# Main_Board.net
KiCad netlist of a schematic drawn in EAGLE
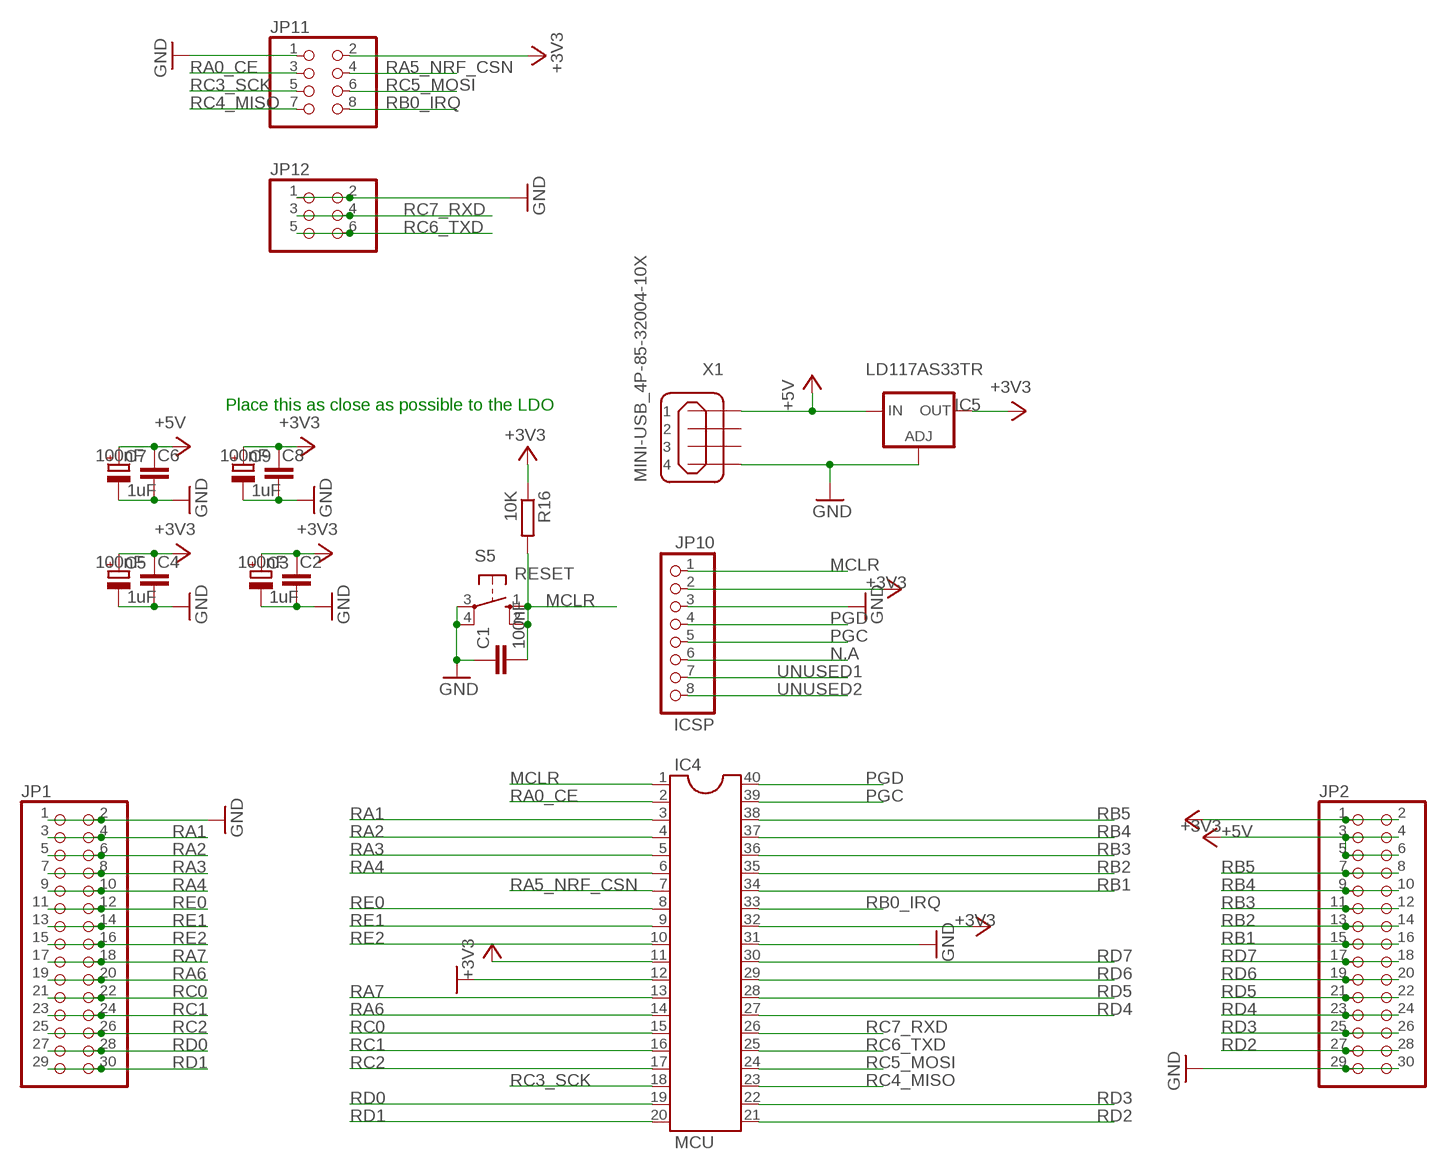
[diagram p0: schematic, sheet 1]
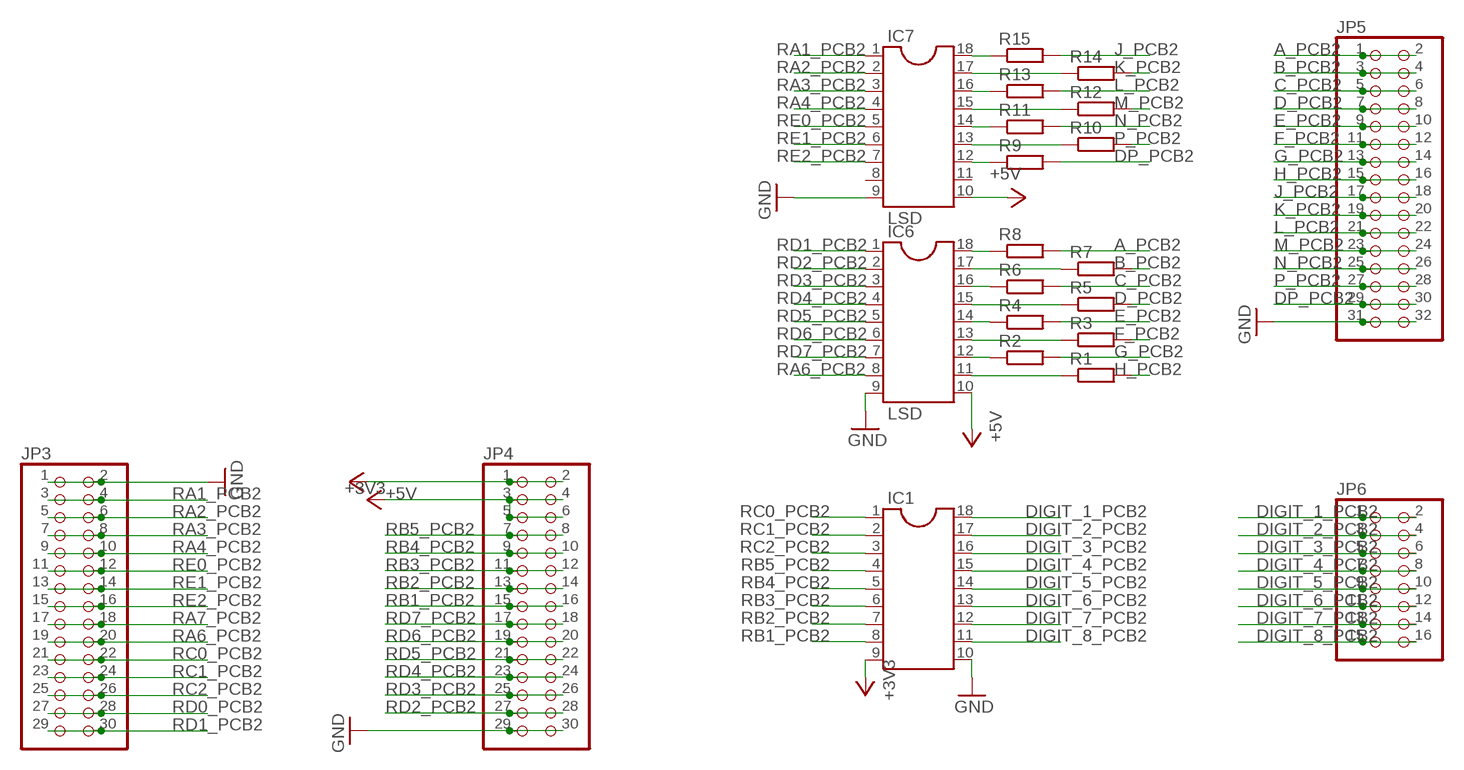
[diagram p1: schematic, sheet 2]
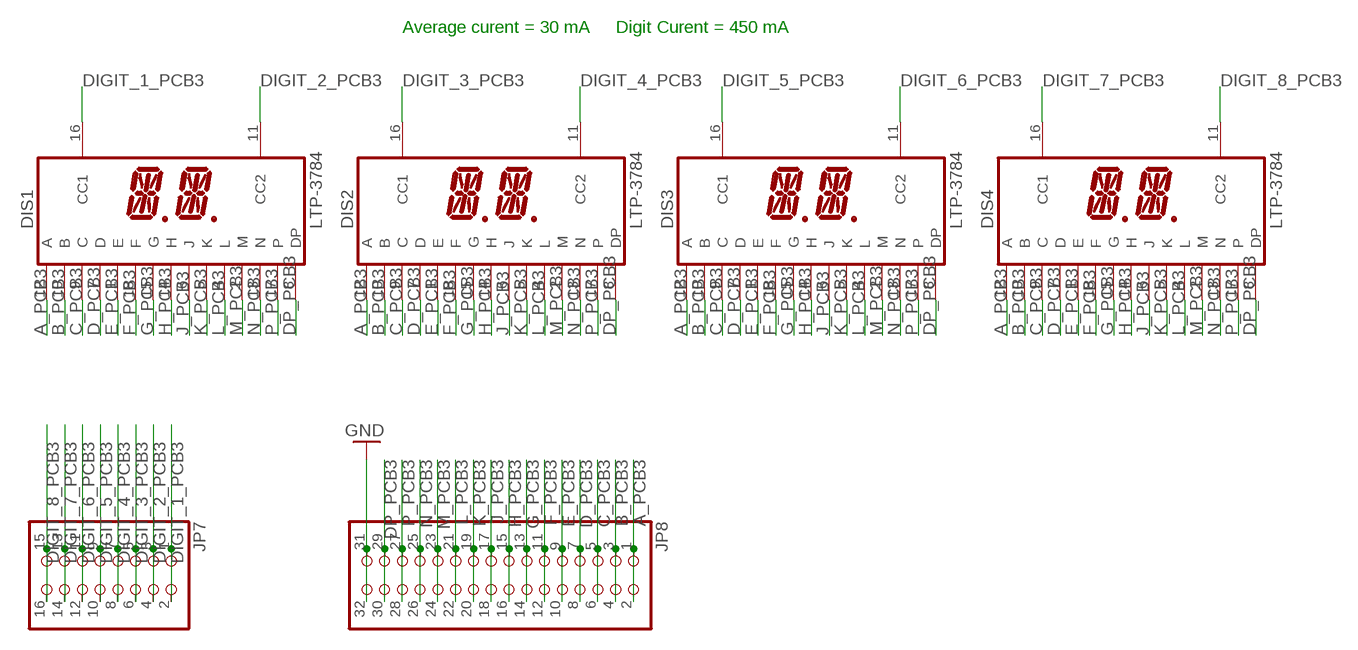
[diagram p2: schematic, sheet 3]

(export (version "E")
  (design (tool "Eeschema 10.0.6"))
  (components
    (comp (ref "IC1")
      (value "DIL18")
      (footprint "eagle-import:DIL18")
      (libsource (lib "eagle-import") (part "DIL18"))
    )
    (comp (ref "IC6")
      (value "LSD")
      (footprint "eagle-import:DIL18")
      (libsource (lib "eagle-import") (part "DIL18"))
    )
    (comp (ref "IC7")
      (value "LSD")
      (footprint "eagle-import:DIL18")
      (libsource (lib "eagle-import") (part "DIL18"))
    )
    (comp (ref "JP3")
      (value "PINHD-2X15")
      (footprint "eagle-import:2X15")
      (libsource (lib "eagle-import") (part "PINHD-2X15"))
    )
    (comp (ref "JP4")
      (value "PINHD-2X15")
      (footprint "eagle-import:2X15")
      (libsource (lib "eagle-import") (part "PINHD-2X15"))
    )
    (comp (ref "JP5")
      (value "PINHD-2X16")
      (footprint "eagle-import:2X16")
      (libsource (lib "eagle-import") (part "PINHD-2X16"))
    )
    (comp (ref "JP6")
      (value "PINHD-2X8")
      (footprint "eagle-import:2X08")
      (libsource (lib "eagle-import") (part "PINHD-2X8"))
    )
    (comp (ref "R1")
      (value "R-EU_R0805")
      (footprint "eagle-import:R0805")
      (libsource (lib "eagle-import") (part "R-EU_R0805"))
    )
    (comp (ref "R2")
      (value "R-EU_R0805")
      (footprint "eagle-import:R0805")
      (libsource (lib "eagle-import") (part "R-EU_R0805"))
    )
    (comp (ref "R3")
      (value "R-EU_R0805")
      (footprint "eagle-import:R0805")
      (libsource (lib "eagle-import") (part "R-EU_R0805"))
    )
    (comp (ref "R4")
      (value "R-EU_R0805")
      (footprint "eagle-import:R0805")
      (libsource (lib "eagle-import") (part "R-EU_R0805"))
    )
    (comp (ref "R5")
      (value "R-EU_R0805")
      (footprint "eagle-import:R0805")
      (libsource (lib "eagle-import") (part "R-EU_R0805"))
    )
    (comp (ref "R6")
      (value "R-EU_R0805")
      (footprint "eagle-import:R0805")
      (libsource (lib "eagle-import") (part "R-EU_R0805"))
    )
    (comp (ref "R7")
      (value "R-EU_R0805")
      (footprint "eagle-import:R0805")
      (libsource (lib "eagle-import") (part "R-EU_R0805"))
    )
    (comp (ref "R8")
      (value "R-EU_R0805")
      (footprint "eagle-import:R0805")
      (libsource (lib "eagle-import") (part "R-EU_R0805"))
    )
    (comp (ref "R9")
      (value "R-EU_R0805")
      (footprint "eagle-import:R0805")
      (libsource (lib "eagle-import") (part "R-EU_R0805"))
    )
    (comp (ref "R10")
      (value "R-EU_R0805")
      (footprint "eagle-import:R0805")
      (libsource (lib "eagle-import") (part "R-EU_R0805"))
    )
    (comp (ref "R11")
      (value "R-EU_R0805")
      (footprint "eagle-import:R0805")
      (libsource (lib "eagle-import") (part "R-EU_R0805"))
    )
    (comp (ref "R12")
      (value "R-EU_R0805")
      (footprint "eagle-import:R0805")
      (libsource (lib "eagle-import") (part "R-EU_R0805"))
    )
    (comp (ref "R13")
      (value "R-EU_R0805")
      (footprint "eagle-import:R0805")
      (libsource (lib "eagle-import") (part "R-EU_R0805"))
    )
    (comp (ref "R14")
      (value "R-EU_R0805")
      (footprint "eagle-import:R0805")
      (libsource (lib "eagle-import") (part "R-EU_R0805"))
    )
    (comp (ref "R15")
      (value "R-EU_R0805")
      (footprint "eagle-import:R0805")
      (libsource (lib "eagle-import") (part "R-EU_R0805"))
    )
    (comp (ref "DIS1")
      (value "LTP-3784")
      (footprint "eagle-import:LTP-3784")
      (libsource (lib "eagle-import") (part "LTP-3784"))
    )
    (comp (ref "DIS2")
      (value "LTP-3784")
      (footprint "eagle-import:LTP-3784")
      (libsource (lib "eagle-import") (part "LTP-3784"))
    )
    (comp (ref "DIS3")
      (value "LTP-3784")
      (footprint "eagle-import:LTP-3784")
      (libsource (lib "eagle-import") (part "LTP-3784"))
    )
    (comp (ref "DIS4")
      (value "LTP-3784")
      (footprint "eagle-import:LTP-3784")
      (libsource (lib "eagle-import") (part "LTP-3784"))
    )
    (comp (ref "JP7")
      (value "PINHD-2X8")
      (footprint "eagle-import:2X08")
      (libsource (lib "eagle-import") (part "PINHD-2X8"))
    )
    (comp (ref "JP8")
      (value "PINHD-2X16")
      (footprint "eagle-import:2X16")
      (libsource (lib "eagle-import") (part "PINHD-2X16"))
    )
    (comp (ref "C1")
      (value "100nF")
      (footprint "eagle-import:C025-025X050")
      (libsource (lib "eagle-import") (part "C-EU025-025X050"))
    )
    (comp (ref "C2")
      (value "100nF")
      (footprint "eagle-import:C025-025X050")
      (libsource (lib "eagle-import") (part "C-EU025-025X050"))
    )
    (comp (ref "C3")
      (value "1uF")
      (footprint "eagle-import:E1,8-4")
      (libsource (lib "eagle-import") (part "CPOL-EUE1.8-4"))
    )
    (comp (ref "C4")
      (value "100nF")
      (footprint "eagle-import:C025-025X050")
      (libsource (lib "eagle-import") (part "C-EU025-025X050"))
    )
    (comp (ref "C5")
      (value "1uF")
      (footprint "eagle-import:E1,8-4")
      (libsource (lib "eagle-import") (part "CPOL-EUE1.8-4"))
    )
    (comp (ref "C6")
      (value "100nF")
      (footprint "eagle-import:C025-025X050")
      (libsource (lib "eagle-import") (part "C-EU025-025X050"))
    )
    (comp (ref "C7")
      (value "1uF")
      (footprint "eagle-import:E1,8-4")
      (libsource (lib "eagle-import") (part "CPOL-EUE1.8-4"))
    )
    (comp (ref "C8")
      (value "100nF")
      (footprint "eagle-import:C025-025X050")
      (libsource (lib "eagle-import") (part "C-EU025-025X050"))
    )
    (comp (ref "C9")
      (value "1uF")
      (footprint "eagle-import:E1,8-4")
      (libsource (lib "eagle-import") (part "CPOL-EUE1.8-4"))
    )
    (comp (ref "IC4")
      (value "MCU")
      (footprint "eagle-import:DIL40")
      (libsource (lib "eagle-import") (part "DIL40"))
    )
    (comp (ref "IC5")
      (value "LD117AS33TR")
      (footprint "eagle-import:SOT223")
      (libsource (lib "eagle-import") (part "LD117A?S33TR"))
    )
    (comp (ref "JP1")
      (value "PINHD-2X15")
      (footprint "eagle-import:2X15")
      (libsource (lib "eagle-import") (part "PINHD-2X15"))
    )
    (comp (ref "JP2")
      (value "PINHD-2X15")
      (footprint "eagle-import:2X15")
      (libsource (lib "eagle-import") (part "PINHD-2X15"))
    )
    (comp (ref "JP10")
      (value "ICSP")
      (footprint "eagle-import:1X08")
      (libsource (lib "eagle-import") (part "PINHD-1X8"))
    )
    (comp (ref "JP11")
      (value "PINHD-2X4")
      (footprint "eagle-import:2X04")
      (libsource (lib "eagle-import") (part "PINHD-2X4"))
    )
    (comp (ref "JP12")
      (value "PINHD-2X3")
      (footprint "eagle-import:2X03")
      (libsource (lib "eagle-import") (part "PINHD-2X3"))
    )
    (comp (ref "R16")
      (value "10K")
      (footprint "eagle-import:0207_10")
      (libsource (lib "eagle-import") (part "R-EU_0207/10"))
    )
    (comp (ref "S5")
      (value "RESET")
      (footprint "eagle-import:B3F-10XX")
      (fields (field (name "MPN") "B3F-1000"))
      (libsource (lib "eagle-import") (part "10-XX"))
    )
    (comp (ref "X1")
      (value "MINI-USB_4P-85-32004-10X")
      (footprint "eagle-import:85-32004-10X")
      (libsource (lib "eagle-import") (part "MINI-USB_4P-85-32004-10X"))
    )
  )
  (nets
    (net (code "1") (name "+3V3") (class "Default")
      (node (ref "C2") (pin "2") (pinfunction "2_2") (pintype "passive"))
      (node (ref "C3") (pin "+") (pinfunction "+_+") (pintype "passive"))
      (node (ref "C4") (pin "2") (pinfunction "2_2") (pintype "passive"))
      (node (ref "C5") (pin "+") (pinfunction "+_+") (pintype "passive"))
      (node (ref "C8") (pin "2") (pinfunction "2_2") (pintype "passive"))
      (node (ref "C9") (pin "+") (pinfunction "+_+") (pintype "passive"))
      (node (ref "IC1") (pin "9") (pinfunction "9_9") (pintype "passive"))
      (node (ref "IC4") (pin "11") (pinfunction "11_11") (pintype "passive"))
      (node (ref "IC4") (pin "32") (pinfunction "32_32") (pintype "passive"))
      (node (ref "IC5") (pin "4") (pinfunction "OUT_4") (pintype "passive"))
      (node (ref "JP10") (pin "2") (pinfunction "2_2") (pintype "passive"))
      (node (ref "JP11") (pin "2") (pinfunction "2_2") (pintype "passive"))
      (node (ref "JP2") (pin "1") (pinfunction "1_1") (pintype "passive"))
      (node (ref "JP2") (pin "2") (pinfunction "2_2") (pintype "passive"))
      (node (ref "JP4") (pin "1") (pinfunction "1_1") (pintype "passive"))
      (node (ref "JP4") (pin "2") (pinfunction "2_2") (pintype "passive"))
      (node (ref "R16") (pin "1") (pinfunction "1_1") (pintype "passive"))
    )
    (net (code "2") (name "+5V") (class "Default")
      (node (ref "C6") (pin "2") (pinfunction "2_2") (pintype "passive"))
      (node (ref "C7") (pin "+") (pinfunction "+_+") (pintype "passive"))
      (node (ref "IC5") (pin "3") (pinfunction "IN_3") (pintype "input"))
      (node (ref "IC6") (pin "10") (pinfunction "10_10") (pintype "passive"))
      (node (ref "IC7") (pin "10") (pinfunction "10_10") (pintype "passive"))
      (node (ref "JP2") (pin "3") (pinfunction "3_3") (pintype "passive"))
      (node (ref "JP2") (pin "4") (pinfunction "4_4") (pintype "passive"))
      (node (ref "JP2") (pin "5") (pinfunction "5_5") (pintype "passive"))
      (node (ref "JP2") (pin "6") (pinfunction "6_6") (pintype "passive"))
      (node (ref "JP4") (pin "3") (pinfunction "3_3") (pintype "passive"))
      (node (ref "JP4") (pin "4") (pinfunction "4_4") (pintype "passive"))
      (node (ref "JP4") (pin "5") (pinfunction "5_5") (pintype "passive"))
      (node (ref "JP4") (pin "6") (pinfunction "6_6") (pintype "passive"))
      (node (ref "X1") (pin "1") (pinfunction "1_1") (pintype "passive"))
    )
    (net (code "3") (name "A_PCB2") (class "Default")
      (node (ref "JP5") (pin "1") (pinfunction "1_1") (pintype "passive"))
      (node (ref "JP5") (pin "2") (pinfunction "2_2") (pintype "passive"))
      (node (ref "R8") (pin "2") (pinfunction "2_2") (pintype "passive"))
    )
    (net (code "4") (name "A_PCB3") (class "Default")
      (node (ref "DIS1") (pin "12") (pinfunction "A_12") (pintype "passive"))
      (node (ref "DIS2") (pin "12") (pinfunction "A_12") (pintype "passive"))
      (node (ref "DIS3") (pin "12") (pinfunction "A_12") (pintype "passive"))
      (node (ref "DIS4") (pin "12") (pinfunction "A_12") (pintype "passive"))
      (node (ref "JP8") (pin "1") (pinfunction "1_1") (pintype "passive"))
      (node (ref "JP8") (pin "2") (pinfunction "2_2") (pintype "passive"))
    )
    (net (code "5") (name "B_PCB2") (class "Default")
      (node (ref "JP5") (pin "3") (pinfunction "3_3") (pintype "passive"))
      (node (ref "JP5") (pin "4") (pinfunction "4_4") (pintype "passive"))
      (node (ref "R7") (pin "2") (pinfunction "2_2") (pintype "passive"))
    )
    (net (code "6") (name "B_PCB3") (class "Default")
      (node (ref "DIS1") (pin "10") (pinfunction "B_10") (pintype "passive"))
      (node (ref "DIS2") (pin "10") (pinfunction "B_10") (pintype "passive"))
      (node (ref "DIS3") (pin "10") (pinfunction "B_10") (pintype "passive"))
      (node (ref "DIS4") (pin "10") (pinfunction "B_10") (pintype "passive"))
      (node (ref "JP8") (pin "3") (pinfunction "3_3") (pintype "passive"))
      (node (ref "JP8") (pin "4") (pinfunction "4_4") (pintype "passive"))
    )
    (net (code "7") (name "C_PCB2") (class "Default")
      (node (ref "JP5") (pin "5") (pinfunction "5_5") (pintype "passive"))
      (node (ref "JP5") (pin "6") (pinfunction "6_6") (pintype "passive"))
      (node (ref "R6") (pin "2") (pinfunction "2_2") (pintype "passive"))
    )
    (net (code "8") (name "C_PCB3") (class "Default")
      (node (ref "DIS1") (pin "9") (pinfunction "C_9") (pintype "passive"))
      (node (ref "DIS2") (pin "9") (pinfunction "C_9") (pintype "passive"))
      (node (ref "DIS3") (pin "9") (pinfunction "C_9") (pintype "passive"))
      (node (ref "DIS4") (pin "9") (pinfunction "C_9") (pintype "passive"))
      (node (ref "JP8") (pin "5") (pinfunction "5_5") (pintype "passive"))
      (node (ref "JP8") (pin "6") (pinfunction "6_6") (pintype "passive"))
    )
    (net (code "9") (name "DIGIT_1_PCB2") (class "Default")
      (node (ref "IC1") (pin "18") (pinfunction "18_18") (pintype "passive"))
      (node (ref "JP6") (pin "1") (pinfunction "1_1") (pintype "passive"))
      (node (ref "JP6") (pin "2") (pinfunction "2_2") (pintype "passive"))
    )
    (net (code "10") (name "DIGIT_1_PCB3") (class "Default")
      (node (ref "DIS1") (pin "16") (pinfunction "CC1_16") (pintype "passive"))
      (node (ref "JP7") (pin "1") (pinfunction "1_1") (pintype "passive"))
      (node (ref "JP7") (pin "2") (pinfunction "2_2") (pintype "passive"))
    )
    (net (code "11") (name "DIGIT_2_PCB2") (class "Default")
      (node (ref "IC1") (pin "17") (pinfunction "17_17") (pintype "passive"))
      (node (ref "JP6") (pin "3") (pinfunction "3_3") (pintype "passive"))
      (node (ref "JP6") (pin "4") (pinfunction "4_4") (pintype "passive"))
    )
    (net (code "12") (name "DIGIT_2_PCB3") (class "Default")
      (node (ref "DIS1") (pin "11") (pinfunction "CC2_11") (pintype "passive"))
      (node (ref "JP7") (pin "3") (pinfunction "3_3") (pintype "passive"))
      (node (ref "JP7") (pin "4") (pinfunction "4_4") (pintype "passive"))
    )
    (net (code "13") (name "DIGIT_3_PCB2") (class "Default")
      (node (ref "IC1") (pin "16") (pinfunction "16_16") (pintype "passive"))
      (node (ref "JP6") (pin "5") (pinfunction "5_5") (pintype "passive"))
      (node (ref "JP6") (pin "6") (pinfunction "6_6") (pintype "passive"))
    )
    (net (code "14") (name "DIGIT_3_PCB3") (class "Default")
      (node (ref "DIS2") (pin "16") (pinfunction "CC1_16") (pintype "passive"))
      (node (ref "JP7") (pin "5") (pinfunction "5_5") (pintype "passive"))
      (node (ref "JP7") (pin "6") (pinfunction "6_6") (pintype "passive"))
    )
    (net (code "15") (name "DIGIT_4_PCB2") (class "Default")
      (node (ref "IC1") (pin "15") (pinfunction "15_15") (pintype "passive"))
      (node (ref "JP6") (pin "7") (pinfunction "7_7") (pintype "passive"))
      (node (ref "JP6") (pin "8") (pinfunction "8_8") (pintype "passive"))
    )
    (net (code "16") (name "DIGIT_4_PCB3") (class "Default")
      (node (ref "DIS2") (pin "11") (pinfunction "CC2_11") (pintype "passive"))
      (node (ref "JP7") (pin "7") (pinfunction "7_7") (pintype "passive"))
      (node (ref "JP7") (pin "8") (pinfunction "8_8") (pintype "passive"))
    )
    (net (code "17") (name "DIGIT_5_PCB2") (class "Default")
      (node (ref "IC1") (pin "14") (pinfunction "14_14") (pintype "passive"))
      (node (ref "JP6") (pin "10") (pinfunction "10_10") (pintype "passive"))
      (node (ref "JP6") (pin "9") (pinfunction "9_9") (pintype "passive"))
    )
    (net (code "18") (name "DIGIT_5_PCB3") (class "Default")
      (node (ref "DIS3") (pin "16") (pinfunction "CC1_16") (pintype "passive"))
      (node (ref "JP7") (pin "10") (pinfunction "10_10") (pintype "passive"))
      (node (ref "JP7") (pin "9") (pinfunction "9_9") (pintype "passive"))
    )
    (net (code "19") (name "DIGIT_6_PCB2") (class "Default")
      (node (ref "IC1") (pin "13") (pinfunction "13_13") (pintype "passive"))
      (node (ref "JP6") (pin "11") (pinfunction "11_11") (pintype "passive"))
      (node (ref "JP6") (pin "12") (pinfunction "12_12") (pintype "passive"))
    )
    (net (code "20") (name "DIGIT_6_PCB3") (class "Default")
      (node (ref "DIS3") (pin "11") (pinfunction "CC2_11") (pintype "passive"))
      (node (ref "JP7") (pin "11") (pinfunction "11_11") (pintype "passive"))
      (node (ref "JP7") (pin "12") (pinfunction "12_12") (pintype "passive"))
    )
    (net (code "21") (name "DIGIT_7_PCB2") (class "Default")
      (node (ref "IC1") (pin "12") (pinfunction "12_12") (pintype "passive"))
      (node (ref "JP6") (pin "13") (pinfunction "13_13") (pintype "passive"))
      (node (ref "JP6") (pin "14") (pinfunction "14_14") (pintype "passive"))
    )
    (net (code "22") (name "DIGIT_7_PCB3") (class "Default")
      (node (ref "DIS4") (pin "16") (pinfunction "CC1_16") (pintype "passive"))
      (node (ref "JP7") (pin "13") (pinfunction "13_13") (pintype "passive"))
      (node (ref "JP7") (pin "14") (pinfunction "14_14") (pintype "passive"))
    )
    (net (code "23") (name "DIGIT_8_PCB2") (class "Default")
      (node (ref "IC1") (pin "11") (pinfunction "11_11") (pintype "passive"))
      (node (ref "JP6") (pin "15") (pinfunction "15_15") (pintype "passive"))
      (node (ref "JP6") (pin "16") (pinfunction "16_16") (pintype "passive"))
    )
    (net (code "24") (name "DIGIT_8_PCB3") (class "Default")
      (node (ref "DIS4") (pin "11") (pinfunction "CC2_11") (pintype "passive"))
      (node (ref "JP7") (pin "15") (pinfunction "15_15") (pintype "passive"))
      (node (ref "JP7") (pin "16") (pinfunction "16_16") (pintype "passive"))
    )
    (net (code "25") (name "DP_PCB2") (class "Default")
      (node (ref "JP5") (pin "29") (pinfunction "29_29") (pintype "passive"))
      (node (ref "JP5") (pin "30") (pinfunction "30_30") (pintype "passive"))
      (node (ref "R9") (pin "2") (pinfunction "2_2") (pintype "passive"))
    )
    (net (code "26") (name "DP_PCB3") (class "Default")
      (node (ref "DIS1") (pin "8") (pinfunction "DP_8") (pintype "passive"))
      (node (ref "DIS2") (pin "8") (pinfunction "DP_8") (pintype "passive"))
      (node (ref "DIS3") (pin "8") (pinfunction "DP_8") (pintype "passive"))
      (node (ref "DIS4") (pin "8") (pinfunction "DP_8") (pintype "passive"))
      (node (ref "JP8") (pin "29") (pinfunction "29_29") (pintype "passive"))
      (node (ref "JP8") (pin "30") (pinfunction "30_30") (pintype "passive"))
    )
    (net (code "27") (name "D_PCB2") (class "Default")
      (node (ref "JP5") (pin "7") (pinfunction "7_7") (pintype "passive"))
      (node (ref "JP5") (pin "8") (pinfunction "8_8") (pintype "passive"))
      (node (ref "R5") (pin "2") (pinfunction "2_2") (pintype "passive"))
    )
    (net (code "28") (name "D_PCB3") (class "Default")
      (node (ref "DIS1") (pin "7") (pinfunction "D_7") (pintype "passive"))
      (node (ref "DIS2") (pin "7") (pinfunction "D_7") (pintype "passive"))
      (node (ref "DIS3") (pin "7") (pinfunction "D_7") (pintype "passive"))
      (node (ref "DIS4") (pin "7") (pinfunction "D_7") (pintype "passive"))
      (node (ref "JP8") (pin "7") (pinfunction "7_7") (pintype "passive"))
      (node (ref "JP8") (pin "8") (pinfunction "8_8") (pintype "passive"))
    )
    (net (code "29") (name "E_PCB2") (class "Default")
      (node (ref "JP5") (pin "10") (pinfunction "10_10") (pintype "passive"))
      (node (ref "JP5") (pin "9") (pinfunction "9_9") (pintype "passive"))
      (node (ref "R4") (pin "2") (pinfunction "2_2") (pintype "passive"))
    )
    (net (code "30") (name "E_PCB3") (class "Default")
      (node (ref "DIS1") (pin "1") (pinfunction "E_1") (pintype "passive"))
      (node (ref "DIS2") (pin "1") (pinfunction "E_1") (pintype "passive"))
      (node (ref "DIS3") (pin "1") (pinfunction "E_1") (pintype "passive"))
      (node (ref "DIS4") (pin "1") (pinfunction "E_1") (pintype "passive"))
      (node (ref "JP8") (pin "10") (pinfunction "10_10") (pintype "passive"))
      (node (ref "JP8") (pin "9") (pinfunction "9_9") (pintype "passive"))
    )
    (net (code "31") (name "F_PCB2") (class "Default")
      (node (ref "JP5") (pin "11") (pinfunction "11_11") (pintype "passive"))
      (node (ref "JP5") (pin "12") (pinfunction "12_12") (pintype "passive"))
      (node (ref "R3") (pin "2") (pinfunction "2_2") (pintype "passive"))
    )
    (net (code "32") (name "F_PCB3") (class "Default")
      (node (ref "DIS1") (pin "18") (pinfunction "F_18") (pintype "passive"))
      (node (ref "DIS2") (pin "18") (pinfunction "F_18") (pintype "passive"))
      (node (ref "DIS3") (pin "18") (pinfunction "F_18") (pintype "passive"))
      (node (ref "DIS4") (pin "18") (pinfunction "F_18") (pintype "passive"))
      (node (ref "JP8") (pin "11") (pinfunction "11_11") (pintype "passive"))
      (node (ref "JP8") (pin "12") (pinfunction "12_12") (pintype "passive"))
    )
    (net (code "33") (name "GND") (class "Default")
      (node (ref "C1") (pin "1") (pinfunction "1_1") (pintype "passive"))
      (node (ref "C2") (pin "1") (pinfunction "1_1") (pintype "passive"))
      (node (ref "C3") (pin "-") (pinfunction "-_-") (pintype "passive"))
      (node (ref "C4") (pin "1") (pinfunction "1_1") (pintype "passive"))
      (node (ref "C5") (pin "-") (pinfunction "-_-") (pintype "passive"))
      (node (ref "C6") (pin "1") (pinfunction "1_1") (pintype "passive"))
      (node (ref "C7") (pin "-") (pinfunction "-_-") (pintype "passive"))
      (node (ref "C8") (pin "1") (pinfunction "1_1") (pintype "passive"))
      (node (ref "C9") (pin "-") (pinfunction "-_-") (pintype "passive"))
      (node (ref "IC1") (pin "10") (pinfunction "10_10") (pintype "passive"))
      (node (ref "IC4") (pin "12") (pinfunction "12_12") (pintype "passive"))
      (node (ref "IC4") (pin "31") (pinfunction "31_31") (pintype "passive"))
      (node (ref "IC5") (pin "1") (pinfunction "ADJ_1") (pintype "input"))
      (node (ref "IC6") (pin "9") (pinfunction "9_9") (pintype "passive"))
      (node (ref "IC7") (pin "9") (pinfunction "9_9") (pintype "passive"))
      (node (ref "JP1") (pin "1") (pinfunction "1_1") (pintype "passive"))
      (node (ref "JP1") (pin "2") (pinfunction "2_2") (pintype "passive"))
      (node (ref "JP10") (pin "3") (pinfunction "3_3") (pintype "passive"))
      (node (ref "JP11") (pin "1") (pinfunction "1_1") (pintype "passive"))
      (node (ref "JP12") (pin "1") (pinfunction "1_1") (pintype "passive"))
      (node (ref "JP12") (pin "2") (pinfunction "2_2") (pintype "passive"))
      (node (ref "JP2") (pin "29") (pinfunction "29_29") (pintype "passive"))
      (node (ref "JP2") (pin "30") (pinfunction "30_30") (pintype "passive"))
      (node (ref "JP3") (pin "1") (pinfunction "1_1") (pintype "passive"))
      (node (ref "JP3") (pin "2") (pinfunction "2_2") (pintype "passive"))
      (node (ref "JP4") (pin "29") (pinfunction "29_29") (pintype "passive"))
      (node (ref "JP4") (pin "30") (pinfunction "30_30") (pintype "passive"))
      (node (ref "JP5") (pin "31") (pinfunction "31_31") (pintype "passive"))
      (node (ref "JP5") (pin "32") (pinfunction "32_32") (pintype "passive"))
      (node (ref "JP8") (pin "31") (pinfunction "31_31") (pintype "passive"))
      (node (ref "JP8") (pin "32") (pinfunction "32_32") (pintype "passive"))
      (node (ref "S5") (pin "3") (pinfunction "P_3") (pintype "passive"))
      (node (ref "S5") (pin "4") (pinfunction "P1_4") (pintype "passive"))
      (node (ref "X1") (pin "4") (pinfunction "4_4") (pintype "passive"))
    )
    (net (code "34") (name "G_PCB2") (class "Default")
      (node (ref "JP5") (pin "13") (pinfunction "13_13") (pintype "passive"))
      (node (ref "JP5") (pin "14") (pinfunction "14_14") (pintype "passive"))
      (node (ref "R2") (pin "2") (pinfunction "2_2") (pintype "passive"))
    )
    (net (code "35") (name "G_PCB3") (class "Default")
      (node (ref "DIS1") (pin "15") (pinfunction "G_15") (pintype "passive"))
      (node (ref "DIS2") (pin "15") (pinfunction "G_15") (pintype "passive"))
      (node (ref "DIS3") (pin "15") (pinfunction "G_15") (pintype "passive"))
      (node (ref "DIS4") (pin "15") (pinfunction "G_15") (pintype "passive"))
      (node (ref "JP8") (pin "13") (pinfunction "13_13") (pintype "passive"))
      (node (ref "JP8") (pin "14") (pinfunction "14_14") (pintype "passive"))
    )
    (net (code "36") (name "H_PCB2") (class "Default")
      (node (ref "JP5") (pin "15") (pinfunction "15_15") (pintype "passive"))
      (node (ref "JP5") (pin "16") (pinfunction "16_16") (pintype "passive"))
      (node (ref "R1") (pin "2") (pinfunction "2_2") (pintype "passive"))
    )
    (net (code "37") (name "H_PCB3") (class "Default")
      (node (ref "DIS1") (pin "14") (pinfunction "H_14") (pintype "passive"))
      (node (ref "DIS2") (pin "14") (pinfunction "H_14") (pintype "passive"))
      (node (ref "DIS3") (pin "14") (pinfunction "H_14") (pintype "passive"))
      (node (ref "DIS4") (pin "14") (pinfunction "H_14") (pintype "passive"))
      (node (ref "JP8") (pin "15") (pinfunction "15_15") (pintype "passive"))
      (node (ref "JP8") (pin "16") (pinfunction "16_16") (pintype "passive"))
    )
    (net (code "38") (name "J_PCB2") (class "Default")
      (node (ref "JP5") (pin "17") (pinfunction "17_17") (pintype "passive"))
      (node (ref "JP5") (pin "18") (pinfunction "18_18") (pintype "passive"))
      (node (ref "R15") (pin "2") (pinfunction "2_2") (pintype "passive"))
    )
    (net (code "39") (name "J_PCB3") (class "Default")
      (node (ref "DIS1") (pin "6") (pinfunction "J_6") (pintype "passive"))
      (node (ref "DIS2") (pin "6") (pinfunction "J_6") (pintype "passive"))
      (node (ref "DIS3") (pin "6") (pinfunction "J_6") (pintype "passive"))
      (node (ref "DIS4") (pin "6") (pinfunction "J_6") (pintype "passive"))
      (node (ref "JP8") (pin "17") (pinfunction "17_17") (pintype "passive"))
      (node (ref "JP8") (pin "18") (pinfunction "18_18") (pintype "passive"))
    )
    (net (code "40") (name "K_PCB2") (class "Default")
      (node (ref "JP5") (pin "19") (pinfunction "19_19") (pintype "passive"))
      (node (ref "JP5") (pin "20") (pinfunction "20_20") (pintype "passive"))
      (node (ref "R14") (pin "2") (pinfunction "2_2") (pintype "passive"))
    )
    (net (code "41") (name "K_PCB3") (class "Default")
      (node (ref "DIS1") (pin "5") (pinfunction "K_5") (pintype "passive"))
      (node (ref "DIS2") (pin "5") (pinfunction "K_5") (pintype "passive"))
      (node (ref "DIS3") (pin "5") (pinfunction "K_5") (pintype "passive"))
      (node (ref "DIS4") (pin "5") (pinfunction "K_5") (pintype "passive"))
      (node (ref "JP8") (pin "19") (pinfunction "19_19") (pintype "passive"))
      (node (ref "JP8") (pin "20") (pinfunction "20_20") (pintype "passive"))
    )
    (net (code "42") (name "L_PCB2") (class "Default")
      (node (ref "JP5") (pin "21") (pinfunction "21_21") (pintype "passive"))
      (node (ref "JP5") (pin "22") (pinfunction "22_22") (pintype "passive"))
      (node (ref "R13") (pin "2") (pinfunction "2_2") (pintype "passive"))
    )
    (net (code "43") (name "L_PCB3") (class "Default")
      (node (ref "DIS1") (pin "4") (pinfunction "L_4") (pintype "passive"))
      (node (ref "DIS2") (pin "4") (pinfunction "L_4") (pintype "passive"))
      (node (ref "DIS3") (pin "4") (pinfunction "L_4") (pintype "passive"))
      (node (ref "DIS4") (pin "4") (pinfunction "L_4") (pintype "passive"))
      (node (ref "JP8") (pin "21") (pinfunction "21_21") (pintype "passive"))
      (node (ref "JP8") (pin "22") (pinfunction "22_22") (pintype "passive"))
    )
    (net (code "44") (name "MCLR") (class "Default")
      (node (ref "C1") (pin "2") (pinfunction "2_2") (pintype "passive"))
      (node (ref "IC4") (pin "1") (pinfunction "1_1") (pintype "passive"))
      (node (ref "JP10") (pin "1") (pinfunction "1_1") (pintype "passive"))
      (node (ref "R16") (pin "2") (pinfunction "2_2") (pintype "passive"))
      (node (ref "S5") (pin "1") (pinfunction "S_1") (pintype "passive"))
      (node (ref "S5") (pin "2") (pinfunction "S1_2") (pintype "passive"))
    )
    (net (code "45") (name "M_PCB2") (class "Default")
      (node (ref "JP5") (pin "23") (pinfunction "23_23") (pintype "passive"))
      (node (ref "JP5") (pin "24") (pinfunction "24_24") (pintype "passive"))
      (node (ref "R12") (pin "2") (pinfunction "2_2") (pintype "passive"))
    )
    (net (code "46") (name "M_PCB3") (class "Default")
      (node (ref "DIS1") (pin "2") (pinfunction "M_2") (pintype "passive"))
      (node (ref "DIS2") (pin "2") (pinfunction "M_2") (pintype "passive"))
      (node (ref "DIS3") (pin "2") (pinfunction "M_2") (pintype "passive"))
      (node (ref "DIS4") (pin "2") (pinfunction "M_2") (pintype "passive"))
      (node (ref "JP8") (pin "23") (pinfunction "23_23") (pintype "passive"))
      (node (ref "JP8") (pin "24") (pinfunction "24_24") (pintype "passive"))
    )
    (net (code "47") (name "N.A") (class "Default")
      (node (ref "JP10") (pin "6") (pinfunction "6_6") (pintype "passive"))
    )
    (net (code "48") (name "N_PCB2") (class "Default")
      (node (ref "JP5") (pin "25") (pinfunction "25_25") (pintype "passive"))
      (node (ref "JP5") (pin "26") (pinfunction "26_26") (pintype "passive"))
      (node (ref "R11") (pin "2") (pinfunction "2_2") (pintype "passive"))
    )
    (net (code "49") (name "N_PCB3") (class "Default")
      (node (ref "DIS1") (pin "13") (pinfunction "N_13") (pintype "passive"))
      (node (ref "DIS2") (pin "13") (pinfunction "N_13") (pintype "passive"))
      (node (ref "DIS3") (pin "13") (pinfunction "N_13") (pintype "passive"))
      (node (ref "DIS4") (pin "13") (pinfunction "N_13") (pintype "passive"))
      (node (ref "JP8") (pin "25") (pinfunction "25_25") (pintype "passive"))
      (node (ref "JP8") (pin "26") (pinfunction "26_26") (pintype "passive"))
    )
    (net (code "50") (name "Net-(IC6-Pad11)") (class "Default")
      (node (ref "IC6") (pin "11") (pinfunction "11_11") (pintype "passive"))
      (node (ref "R1") (pin "1") (pinfunction "1_1") (pintype "passive"))
    )
    (net (code "51") (name "Net-(IC6-Pad12)") (class "Default")
      (node (ref "IC6") (pin "12") (pinfunction "12_12") (pintype "passive"))
      (node (ref "R2") (pin "1") (pinfunction "1_1") (pintype "passive"))
    )
    (net (code "52") (name "Net-(IC6-Pad13)") (class "Default")
      (node (ref "IC6") (pin "13") (pinfunction "13_13") (pintype "passive"))
      (node (ref "R3") (pin "1") (pinfunction "1_1") (pintype "passive"))
    )
    (net (code "53") (name "Net-(IC6-Pad14)") (class "Default")
      (node (ref "IC6") (pin "14") (pinfunction "14_14") (pintype "passive"))
      (node (ref "R4") (pin "1") (pinfunction "1_1") (pintype "passive"))
    )
    (net (code "54") (name "Net-(IC6-Pad15)") (class "Default")
      (node (ref "IC6") (pin "15") (pinfunction "15_15") (pintype "passive"))
      (node (ref "R5") (pin "1") (pinfunction "1_1") (pintype "passive"))
    )
    (net (code "55") (name "Net-(IC6-Pad16)") (class "Default")
      (node (ref "IC6") (pin "16") (pinfunction "16_16") (pintype "passive"))
      (node (ref "R6") (pin "1") (pinfunction "1_1") (pintype "passive"))
    )
    (net (code "56") (name "Net-(IC6-Pad17)") (class "Default")
      (node (ref "IC6") (pin "17") (pinfunction "17_17") (pintype "passive"))
      (node (ref "R7") (pin "1") (pinfunction "1_1") (pintype "passive"))
    )
    (net (code "57") (name "Net-(IC6-Pad18)") (class "Default")
      (node (ref "IC6") (pin "18") (pinfunction "18_18") (pintype "passive"))
      (node (ref "R8") (pin "1") (pinfunction "1_1") (pintype "passive"))
    )
    (net (code "58") (name "Net-(IC7-Pad12)") (class "Default")
      (node (ref "IC7") (pin "12") (pinfunction "12_12") (pintype "passive"))
      (node (ref "R9") (pin "1") (pinfunction "1_1") (pintype "passive"))
    )
    (net (code "59") (name "Net-(IC7-Pad13)") (class "Default")
      (node (ref "IC7") (pin "13") (pinfunction "13_13") (pintype "passive"))
      (node (ref "R10") (pin "1") (pinfunction "1_1") (pintype "passive"))
    )
    (net (code "60") (name "Net-(IC7-Pad14)") (class "Default")
      (node (ref "IC7") (pin "14") (pinfunction "14_14") (pintype "passive"))
      (node (ref "R11") (pin "1") (pinfunction "1_1") (pintype "passive"))
    )
    (net (code "61") (name "Net-(IC7-Pad15)") (class "Default")
      (node (ref "IC7") (pin "15") (pinfunction "15_15") (pintype "passive"))
      (node (ref "R12") (pin "1") (pinfunction "1_1") (pintype "passive"))
    )
    (net (code "62") (name "Net-(IC7-Pad16)") (class "Default")
      (node (ref "IC7") (pin "16") (pinfunction "16_16") (pintype "passive"))
      (node (ref "R13") (pin "1") (pinfunction "1_1") (pintype "passive"))
    )
    (net (code "63") (name "Net-(IC7-Pad17)") (class "Default")
      (node (ref "IC7") (pin "17") (pinfunction "17_17") (pintype "passive"))
      (node (ref "R14") (pin "1") (pinfunction "1_1") (pintype "passive"))
    )
    (net (code "64") (name "Net-(IC7-Pad18)") (class "Default")
      (node (ref "IC7") (pin "18") (pinfunction "18_18") (pintype "passive"))
      (node (ref "R15") (pin "1") (pinfunction "1_1") (pintype "passive"))
    )
    (net (code "65") (name "PGC") (class "Default")
      (node (ref "IC4") (pin "39") (pinfunction "39_39") (pintype "passive"))
      (node (ref "JP10") (pin "5") (pinfunction "5_5") (pintype "passive"))
    )
    (net (code "66") (name "PGD") (class "Default")
      (node (ref "IC4") (pin "40") (pinfunction "40_40") (pintype "passive"))
      (node (ref "JP10") (pin "4") (pinfunction "4_4") (pintype "passive"))
    )
    (net (code "67") (name "P_PCB2") (class "Default")
      (node (ref "JP5") (pin "27") (pinfunction "27_27") (pintype "passive"))
      (node (ref "JP5") (pin "28") (pinfunction "28_28") (pintype "passive"))
      (node (ref "R10") (pin "2") (pinfunction "2_2") (pintype "passive"))
    )
    (net (code "68") (name "P_PCB3") (class "Default")
      (node (ref "DIS1") (pin "17") (pinfunction "P_17") (pintype "passive"))
      (node (ref "DIS2") (pin "17") (pinfunction "P_17") (pintype "passive"))
      (node (ref "DIS3") (pin "17") (pinfunction "P_17") (pintype "passive"))
      (node (ref "DIS4") (pin "17") (pinfunction "P_17") (pintype "passive"))
      (node (ref "JP8") (pin "27") (pinfunction "27_27") (pintype "passive"))
      (node (ref "JP8") (pin "28") (pinfunction "28_28") (pintype "passive"))
    )
    (net (code "69") (name "RA0_CE") (class "Default")
      (node (ref "IC4") (pin "2") (pinfunction "2_2") (pintype "passive"))
      (node (ref "JP11") (pin "3") (pinfunction "3_3") (pintype "passive"))
    )
    (net (code "70") (name "RA1") (class "Default")
      (node (ref "IC4") (pin "3") (pinfunction "3_3") (pintype "passive"))
      (node (ref "JP1") (pin "3") (pinfunction "3_3") (pintype "passive"))
      (node (ref "JP1") (pin "4") (pinfunction "4_4") (pintype "passive"))
    )
    (net (code "71") (name "RA1_PCB2") (class "Default")
      (node (ref "IC7") (pin "1") (pinfunction "1_1") (pintype "passive"))
      (node (ref "JP3") (pin "3") (pinfunction "3_3") (pintype "passive"))
      (node (ref "JP3") (pin "4") (pinfunction "4_4") (pintype "passive"))
    )
    (net (code "72") (name "RA2") (class "Default")
      (node (ref "IC4") (pin "4") (pinfunction "4_4") (pintype "passive"))
      (node (ref "JP1") (pin "5") (pinfunction "5_5") (pintype "passive"))
      (node (ref "JP1") (pin "6") (pinfunction "6_6") (pintype "passive"))
    )
    (net (code "73") (name "RA2_PCB2") (class "Default")
      (node (ref "IC7") (pin "2") (pinfunction "2_2") (pintype "passive"))
      (node (ref "JP3") (pin "5") (pinfunction "5_5") (pintype "passive"))
      (node (ref "JP3") (pin "6") (pinfunction "6_6") (pintype "passive"))
    )
    (net (code "74") (name "RA3") (class "Default")
      (node (ref "IC4") (pin "5") (pinfunction "5_5") (pintype "passive"))
      (node (ref "JP1") (pin "7") (pinfunction "7_7") (pintype "passive"))
      (node (ref "JP1") (pin "8") (pinfunction "8_8") (pintype "passive"))
    )
    (net (code "75") (name "RA3_PCB2") (class "Default")
      (node (ref "IC7") (pin "3") (pinfunction "3_3") (pintype "passive"))
      (node (ref "JP3") (pin "7") (pinfunction "7_7") (pintype "passive"))
      (node (ref "JP3") (pin "8") (pinfunction "8_8") (pintype "passive"))
    )
    (net (code "76") (name "RA4") (class "Default")
      (node (ref "IC4") (pin "6") (pinfunction "6_6") (pintype "passive"))
      (node (ref "JP1") (pin "10") (pinfunction "10_10") (pintype "passive"))
      (node (ref "JP1") (pin "9") (pinfunction "9_9") (pintype "passive"))
    )
    (net (code "77") (name "RA4_PCB2") (class "Default")
      (node (ref "IC7") (pin "4") (pinfunction "4_4") (pintype "passive"))
      (node (ref "JP3") (pin "10") (pinfunction "10_10") (pintype "passive"))
      (node (ref "JP3") (pin "9") (pinfunction "9_9") (pintype "passive"))
    )
    (net (code "78") (name "RA5_NRF_CSN") (class "Default")
      (node (ref "IC4") (pin "7") (pinfunction "7_7") (pintype "passive"))
      (node (ref "JP11") (pin "4") (pinfunction "4_4") (pintype "passive"))
    )
    (net (code "79") (name "RA6") (class "Default")
      (node (ref "IC4") (pin "14") (pinfunction "14_14") (pintype "passive"))
      (node (ref "JP1") (pin "19") (pinfunction "19_19") (pintype "passive"))
      (node (ref "JP1") (pin "20") (pinfunction "20_20") (pintype "passive"))
    )
    (net (code "80") (name "RA6_PCB2") (class "Default")
      (node (ref "IC6") (pin "8") (pinfunction "8_8") (pintype "passive"))
      (node (ref "JP3") (pin "19") (pinfunction "19_19") (pintype "passive"))
      (node (ref "JP3") (pin "20") (pinfunction "20_20") (pintype "passive"))
    )
    (net (code "81") (name "RA7") (class "Default")
      (node (ref "IC4") (pin "13") (pinfunction "13_13") (pintype "passive"))
      (node (ref "JP1") (pin "17") (pinfunction "17_17") (pintype "passive"))
      (node (ref "JP1") (pin "18") (pinfunction "18_18") (pintype "passive"))
    )
    (net (code "82") (name "RA7_PCB2") (class "Default")
      (node (ref "JP3") (pin "17") (pinfunction "17_17") (pintype "passive"))
      (node (ref "JP3") (pin "18") (pinfunction "18_18") (pintype "passive"))
    )
    (net (code "83") (name "RB0_IRQ") (class "Default")
      (node (ref "IC4") (pin "33") (pinfunction "33_33") (pintype "passive"))
      (node (ref "JP11") (pin "8") (pinfunction "8_8") (pintype "passive"))
    )
    (net (code "84") (name "RB1") (class "Default")
      (node (ref "IC4") (pin "34") (pinfunction "34_34") (pintype "passive"))
      (node (ref "JP2") (pin "15") (pinfunction "15_15") (pintype "passive"))
      (node (ref "JP2") (pin "16") (pinfunction "16_16") (pintype "passive"))
    )
    (net (code "85") (name "RB1_PCB2") (class "Default")
      (node (ref "IC1") (pin "8") (pinfunction "8_8") (pintype "passive"))
      (node (ref "JP4") (pin "15") (pinfunction "15_15") (pintype "passive"))
      (node (ref "JP4") (pin "16") (pinfunction "16_16") (pintype "passive"))
    )
    (net (code "86") (name "RB2") (class "Default")
      (node (ref "IC4") (pin "35") (pinfunction "35_35") (pintype "passive"))
      (node (ref "JP2") (pin "13") (pinfunction "13_13") (pintype "passive"))
      (node (ref "JP2") (pin "14") (pinfunction "14_14") (pintype "passive"))
    )
    (net (code "87") (name "RB2_PCB2") (class "Default")
      (node (ref "IC1") (pin "7") (pinfunction "7_7") (pintype "passive"))
      (node (ref "JP4") (pin "13") (pinfunction "13_13") (pintype "passive"))
      (node (ref "JP4") (pin "14") (pinfunction "14_14") (pintype "passive"))
    )
    (net (code "88") (name "RB3") (class "Default")
      (node (ref "IC4") (pin "36") (pinfunction "36_36") (pintype "passive"))
      (node (ref "JP2") (pin "11") (pinfunction "11_11") (pintype "passive"))
      (node (ref "JP2") (pin "12") (pinfunction "12_12") (pintype "passive"))
    )
    (net (code "89") (name "RB3_PCB2") (class "Default")
      (node (ref "IC1") (pin "6") (pinfunction "6_6") (pintype "passive"))
      (node (ref "JP4") (pin "11") (pinfunction "11_11") (pintype "passive"))
      (node (ref "JP4") (pin "12") (pinfunction "12_12") (pintype "passive"))
    )
    (net (code "90") (name "RB4") (class "Default")
      (node (ref "IC4") (pin "37") (pinfunction "37_37") (pintype "passive"))
      (node (ref "JP2") (pin "10") (pinfunction "10_10") (pintype "passive"))
      (node (ref "JP2") (pin "9") (pinfunction "9_9") (pintype "passive"))
    )
    (net (code "91") (name "RB4_PCB2") (class "Default")
      (node (ref "IC1") (pin "5") (pinfunction "5_5") (pintype "passive"))
      (node (ref "JP4") (pin "10") (pinfunction "10_10") (pintype "passive"))
      (node (ref "JP4") (pin "9") (pinfunction "9_9") (pintype "passive"))
    )
    (net (code "92") (name "RB5") (class "Default")
      (node (ref "IC4") (pin "38") (pinfunction "38_38") (pintype "passive"))
      (node (ref "JP2") (pin "7") (pinfunction "7_7") (pintype "passive"))
      (node (ref "JP2") (pin "8") (pinfunction "8_8") (pintype "passive"))
    )
    (net (code "93") (name "RB5_PCB2") (class "Default")
      (node (ref "IC1") (pin "4") (pinfunction "4_4") (pintype "passive"))
      (node (ref "JP4") (pin "7") (pinfunction "7_7") (pintype "passive"))
      (node (ref "JP4") (pin "8") (pinfunction "8_8") (pintype "passive"))
    )
    (net (code "94") (name "RC0") (class "Default")
      (node (ref "IC4") (pin "15") (pinfunction "15_15") (pintype "passive"))
      (node (ref "JP1") (pin "21") (pinfunction "21_21") (pintype "passive"))
      (node (ref "JP1") (pin "22") (pinfunction "22_22") (pintype "passive"))
    )
    (net (code "95") (name "RC0_PCB2") (class "Default")
      (node (ref "IC1") (pin "1") (pinfunction "1_1") (pintype "passive"))
      (node (ref "JP3") (pin "21") (pinfunction "21_21") (pintype "passive"))
      (node (ref "JP3") (pin "22") (pinfunction "22_22") (pintype "passive"))
    )
    (net (code "96") (name "RC1") (class "Default")
      (node (ref "IC4") (pin "16") (pinfunction "16_16") (pintype "passive"))
      (node (ref "JP1") (pin "23") (pinfunction "23_23") (pintype "passive"))
      (node (ref "JP1") (pin "24") (pinfunction "24_24") (pintype "passive"))
    )
    (net (code "97") (name "RC1_PCB2") (class "Default")
      (node (ref "IC1") (pin "2") (pinfunction "2_2") (pintype "passive"))
      (node (ref "JP3") (pin "23") (pinfunction "23_23") (pintype "passive"))
      (node (ref "JP3") (pin "24") (pinfunction "24_24") (pintype "passive"))
    )
    (net (code "98") (name "RC2") (class "Default")
      (node (ref "IC4") (pin "17") (pinfunction "17_17") (pintype "passive"))
      (node (ref "JP1") (pin "25") (pinfunction "25_25") (pintype "passive"))
      (node (ref "JP1") (pin "26") (pinfunction "26_26") (pintype "passive"))
    )
    (net (code "99") (name "RC2_PCB2") (class "Default")
      (node (ref "IC1") (pin "3") (pinfunction "3_3") (pintype "passive"))
      (node (ref "JP3") (pin "25") (pinfunction "25_25") (pintype "passive"))
      (node (ref "JP3") (pin "26") (pinfunction "26_26") (pintype "passive"))
    )
    (net (code "100") (name "RC3_SCK") (class "Default")
      (node (ref "IC4") (pin "18") (pinfunction "18_18") (pintype "passive"))
      (node (ref "JP11") (pin "5") (pinfunction "5_5") (pintype "passive"))
    )
    (net (code "101") (name "RC4_MISO") (class "Default")
      (node (ref "IC4") (pin "23") (pinfunction "23_23") (pintype "passive"))
      (node (ref "JP11") (pin "7") (pinfunction "7_7") (pintype "passive"))
    )
    (net (code "102") (name "RC5_MOSI") (class "Default")
      (node (ref "IC4") (pin "24") (pinfunction "24_24") (pintype "passive"))
      (node (ref "JP11") (pin "6") (pinfunction "6_6") (pintype "passive"))
    )
    (net (code "103") (name "RC6_TXD") (class "Default")
      (node (ref "IC4") (pin "25") (pinfunction "25_25") (pintype "passive"))
      (node (ref "JP12") (pin "5") (pinfunction "5_5") (pintype "passive"))
      (node (ref "JP12") (pin "6") (pinfunction "6_6") (pintype "passive"))
    )
    (net (code "104") (name "RC7_RXD") (class "Default")
      (node (ref "IC4") (pin "26") (pinfunction "26_26") (pintype "passive"))
      (node (ref "JP12") (pin "3") (pinfunction "3_3") (pintype "passive"))
      (node (ref "JP12") (pin "4") (pinfunction "4_4") (pintype "passive"))
    )
    (net (code "105") (name "RD0") (class "Default")
      (node (ref "IC4") (pin "19") (pinfunction "19_19") (pintype "passive"))
      (node (ref "JP1") (pin "27") (pinfunction "27_27") (pintype "passive"))
      (node (ref "JP1") (pin "28") (pinfunction "28_28") (pintype "passive"))
    )
    (net (code "106") (name "RD0_PCB2") (class "Default")
      (node (ref "JP3") (pin "27") (pinfunction "27_27") (pintype "passive"))
      (node (ref "JP3") (pin "28") (pinfunction "28_28") (pintype "passive"))
    )
    (net (code "107") (name "RD1") (class "Default")
      (node (ref "IC4") (pin "20") (pinfunction "20_20") (pintype "passive"))
      (node (ref "JP1") (pin "29") (pinfunction "29_29") (pintype "passive"))
      (node (ref "JP1") (pin "30") (pinfunction "30_30") (pintype "passive"))
    )
    (net (code "108") (name "RD1_PCB2") (class "Default")
      (node (ref "IC6") (pin "1") (pinfunction "1_1") (pintype "passive"))
      (node (ref "JP3") (pin "29") (pinfunction "29_29") (pintype "passive"))
      (node (ref "JP3") (pin "30") (pinfunction "30_30") (pintype "passive"))
    )
    (net (code "109") (name "RD2") (class "Default")
      (node (ref "IC4") (pin "21") (pinfunction "21_21") (pintype "passive"))
      (node (ref "JP2") (pin "27") (pinfunction "27_27") (pintype "passive"))
      (node (ref "JP2") (pin "28") (pinfunction "28_28") (pintype "passive"))
    )
    (net (code "110") (name "RD2_PCB2") (class "Default")
      (node (ref "IC6") (pin "2") (pinfunction "2_2") (pintype "passive"))
      (node (ref "JP4") (pin "27") (pinfunction "27_27") (pintype "passive"))
      (node (ref "JP4") (pin "28") (pinfunction "28_28") (pintype "passive"))
    )
    (net (code "111") (name "RD3") (class "Default")
      (node (ref "IC4") (pin "22") (pinfunction "22_22") (pintype "passive"))
      (node (ref "JP2") (pin "25") (pinfunction "25_25") (pintype "passive"))
      (node (ref "JP2") (pin "26") (pinfunction "26_26") (pintype "passive"))
    )
    (net (code "112") (name "RD3_PCB2") (class "Default")
      (node (ref "IC6") (pin "3") (pinfunction "3_3") (pintype "passive"))
      (node (ref "JP4") (pin "25") (pinfunction "25_25") (pintype "passive"))
      (node (ref "JP4") (pin "26") (pinfunction "26_26") (pintype "passive"))
    )
    (net (code "113") (name "RD4") (class "Default")
      (node (ref "IC4") (pin "27") (pinfunction "27_27") (pintype "passive"))
      (node (ref "JP2") (pin "23") (pinfunction "23_23") (pintype "passive"))
      (node (ref "JP2") (pin "24") (pinfunction "24_24") (pintype "passive"))
    )
    (net (code "114") (name "RD4_PCB2") (class "Default")
      (node (ref "IC6") (pin "4") (pinfunction "4_4") (pintype "passive"))
      (node (ref "JP4") (pin "23") (pinfunction "23_23") (pintype "passive"))
      (node (ref "JP4") (pin "24") (pinfunction "24_24") (pintype "passive"))
    )
    (net (code "115") (name "RD5") (class "Default")
      (node (ref "IC4") (pin "28") (pinfunction "28_28") (pintype "passive"))
      (node (ref "JP2") (pin "21") (pinfunction "21_21") (pintype "passive"))
      (node (ref "JP2") (pin "22") (pinfunction "22_22") (pintype "passive"))
    )
    (net (code "116") (name "RD5_PCB2") (class "Default")
      (node (ref "IC6") (pin "5") (pinfunction "5_5") (pintype "passive"))
      (node (ref "JP4") (pin "21") (pinfunction "21_21") (pintype "passive"))
      (node (ref "JP4") (pin "22") (pinfunction "22_22") (pintype "passive"))
    )
    (net (code "117") (name "RD6") (class "Default")
      (node (ref "IC4") (pin "29") (pinfunction "29_29") (pintype "passive"))
      (node (ref "JP2") (pin "19") (pinfunction "19_19") (pintype "passive"))
      (node (ref "JP2") (pin "20") (pinfunction "20_20") (pintype "passive"))
    )
    (net (code "118") (name "RD6_PCB2") (class "Default")
      (node (ref "IC6") (pin "6") (pinfunction "6_6") (pintype "passive"))
      (node (ref "JP4") (pin "19") (pinfunction "19_19") (pintype "passive"))
      (node (ref "JP4") (pin "20") (pinfunction "20_20") (pintype "passive"))
    )
    (net (code "119") (name "RD7") (class "Default")
      (node (ref "IC4") (pin "30") (pinfunction "30_30") (pintype "passive"))
      (node (ref "JP2") (pin "17") (pinfunction "17_17") (pintype "passive"))
      (node (ref "JP2") (pin "18") (pinfunction "18_18") (pintype "passive"))
    )
    (net (code "120") (name "RD7_PCB2") (class "Default")
      (node (ref "IC6") (pin "7") (pinfunction "7_7") (pintype "passive"))
      (node (ref "JP4") (pin "17") (pinfunction "17_17") (pintype "passive"))
      (node (ref "JP4") (pin "18") (pinfunction "18_18") (pintype "passive"))
    )
    (net (code "121") (name "RE0") (class "Default")
      (node (ref "IC4") (pin "8") (pinfunction "8_8") (pintype "passive"))
      (node (ref "JP1") (pin "11") (pinfunction "11_11") (pintype "passive"))
      (node (ref "JP1") (pin "12") (pinfunction "12_12") (pintype "passive"))
    )
    (net (code "122") (name "RE0_PCB2") (class "Default")
      (node (ref "IC7") (pin "5") (pinfunction "5_5") (pintype "passive"))
      (node (ref "JP3") (pin "11") (pinfunction "11_11") (pintype "passive"))
      (node (ref "JP3") (pin "12") (pinfunction "12_12") (pintype "passive"))
    )
    (net (code "123") (name "RE1") (class "Default")
      (node (ref "IC4") (pin "9") (pinfunction "9_9") (pintype "passive"))
      (node (ref "JP1") (pin "13") (pinfunction "13_13") (pintype "passive"))
      (node (ref "JP1") (pin "14") (pinfunction "14_14") (pintype "passive"))
    )
    (net (code "124") (name "RE1_PCB2") (class "Default")
      (node (ref "IC7") (pin "6") (pinfunction "6_6") (pintype "passive"))
      (node (ref "JP3") (pin "13") (pinfunction "13_13") (pintype "passive"))
      (node (ref "JP3") (pin "14") (pinfunction "14_14") (pintype "passive"))
    )
    (net (code "125") (name "RE2") (class "Default")
      (node (ref "IC4") (pin "10") (pinfunction "10_10") (pintype "passive"))
      (node (ref "JP1") (pin "15") (pinfunction "15_15") (pintype "passive"))
      (node (ref "JP1") (pin "16") (pinfunction "16_16") (pintype "passive"))
    )
    (net (code "126") (name "RE2_PCB2") (class "Default")
      (node (ref "IC7") (pin "7") (pinfunction "7_7") (pintype "passive"))
      (node (ref "JP3") (pin "15") (pinfunction "15_15") (pintype "passive"))
      (node (ref "JP3") (pin "16") (pinfunction "16_16") (pintype "passive"))
    )
    (net (code "127") (name "UNUSED1") (class "Default")
      (node (ref "JP10") (pin "7") (pinfunction "7_7") (pintype "passive"))
    )
    (net (code "128") (name "UNUSED2") (class "Default")
      (node (ref "JP10") (pin "8") (pinfunction "8_8") (pintype "passive"))
    )
    (net (code "129") (name "unconnected-(IC7-Pad8)") (class "Default")
      (node (ref "IC7") (pin "8") (pinfunction "8_8") (pintype "passive"))
    )
    (net (code "130") (name "unconnected-(IC7-Pad11)") (class "Default")
      (node (ref "IC7") (pin "11") (pinfunction "11_11") (pintype "passive"))
    )
    (net (code "131") (name "unconnected-(X1-Pad2)") (class "Default")
      (node (ref "X1") (pin "2") (pinfunction "2_2") (pintype "passive"))
    )
    (net (code "132") (name "unconnected-(X1-Pad3)") (class "Default")
      (node (ref "X1") (pin "3") (pinfunction "3_3") (pintype "passive"))
    )
  )
)
